# vasttrapi_pmu.net
KiCad netlist of a schematic drawn in EAGLE
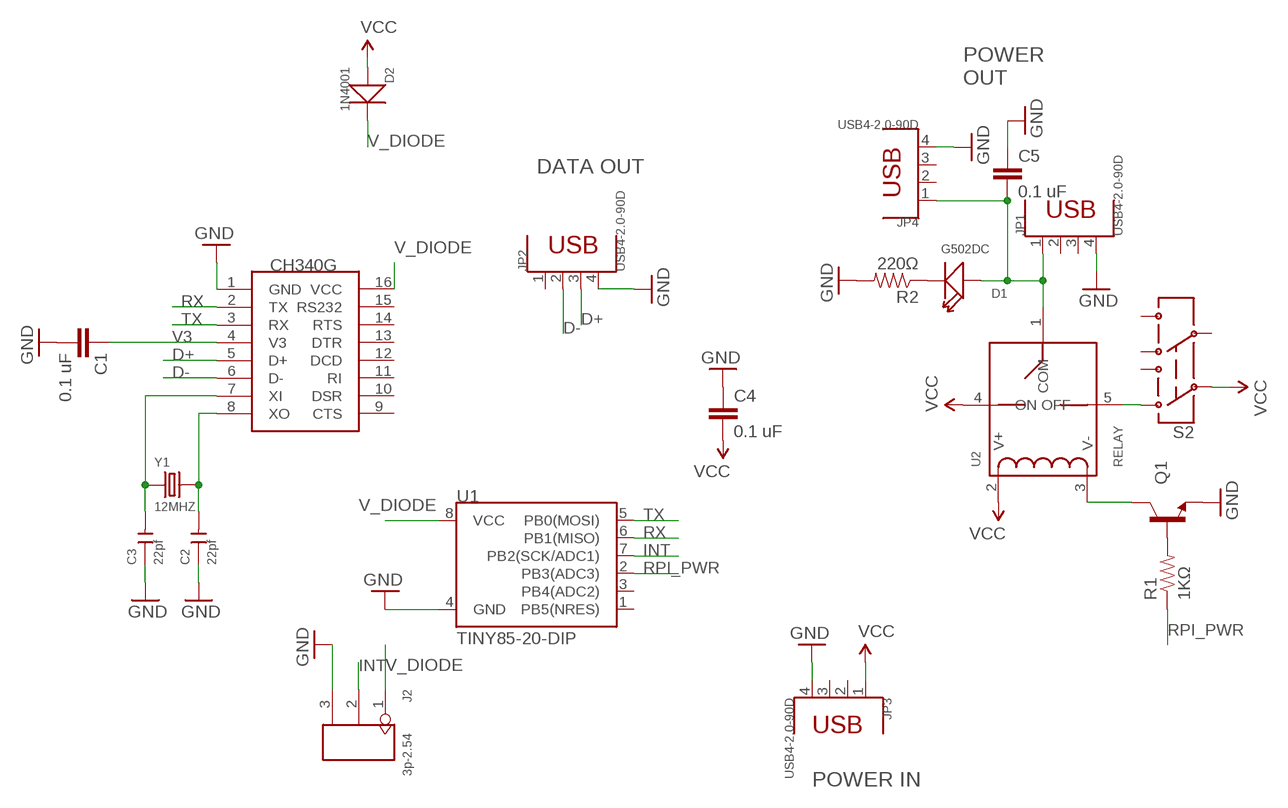
[diagram p0: schematic, sheet 1]

(export (version "E")
  (design (tool "Eeschema 10.0.6"))
  (components
    (comp (ref "C1")
      (value "0.1 uF")
      (footprint "eagle-import:CAP-PTH-SMALL-KIT")
      (libsource (lib "eagle-import") (part "0.1UF-50V-20%(PTH)KIT-EZ"))
    )
    (comp (ref "C2")
      (value "22pf")
      (footprint "eagle-import:CERAMIC-2.54")
      (fields (field (name "MPN") "CT4-0805CG220J101F3"))
      (libsource (lib "eagle-import") (part "DIP-CERAMIC-22PF-100V-5%-NPO(D5.0MM)"))
    )
    (comp (ref "C3")
      (value "22pf")
      (footprint "eagle-import:CERAMIC-2.54")
      (fields (field (name "MPN") "CT4-0805CG220J101F3"))
      (libsource (lib "eagle-import") (part "DIP-CERAMIC-22PF-100V-5%-NPO(D5.0MM)"))
    )
    (comp (ref "C4")
      (value "0.1 uF")
      (footprint "eagle-import:CAP-PTH-SMALL-KIT")
      (libsource (lib "eagle-import") (part "0.1UF-50V-20%(PTH)KIT-EZ"))
    )
    (comp (ref "C5")
      (value "0.1 uF")
      (footprint "eagle-import:CAP-PTH-SMALL-KIT")
      (libsource (lib "eagle-import") (part "0.1UF-50V-20%(PTH)KIT-EZ"))
    )
    (comp (ref "D1")
      (value "G502DC")
      (footprint "eagle-import:LED2-2.54-D5.0MM")
      (libsource (lib "eagle-import") (part "DIP-LED-GREEN-GREEN(2P-D5MM)"))
    )
    (comp (ref "D2")
      (value "1N4001")
      (footprint "eagle-import:DO-41")
      (libsource (lib "eagle-import") (part "DIP-DIODE-50V-1A-1N4001(DO-41)"))
    )
    (comp (ref "J2")
      (value "3p-2.54")
      (footprint "eagle-import:H3-2.54")
      (fields (field (name "MPN") "F185-1103A0BSYA1"))
      (libsource (lib "eagle-import") (part "DIP-BLACK-FEMALE-HEADER-VERT(3P-2.54)"))
    )
    (comp (ref "JP1")
      (value "USB4-2.0-90D")
      (footprint "eagle-import:USB4+2P-2.0-90D")
      (libsource (lib "eagle-import") (part "DIP-USB-A-TYPE-FMAL(4+2P-2.0-90D)"))
    )
    (comp (ref "JP2")
      (value "USB4-2.0-90D")
      (footprint "eagle-import:USB4+2P-2.0-90D")
      (libsource (lib "eagle-import") (part "DIP-USB-A-TYPE-FMAL(4+2P-2.0-90D)"))
    )
    (comp (ref "JP3")
      (value "USB4-2.0-90D")
      (footprint "eagle-import:USB4+2P-2.0-90D")
      (libsource (lib "eagle-import") (part "DIP-USB-A-TYPE-FMAL(4+2P-2.0-90D)"))
    )
    (comp (ref "JP4")
      (value "USB4-2.0-90D")
      (footprint "eagle-import:USB4+2P-2.0-90D")
      (libsource (lib "eagle-import") (part "DIP-USB-A-TYPE-FMAL(4+2P-2.0-90D)"))
    )
    (comp (ref "Q1")
      (value "TRANSISTOR_NPNBC547")
      (footprint "eagle-import:TO-92-AMMO")
      (libsource (lib "eagle-import") (part "TRANSISTOR_NPNBC547"))
    )
    (comp (ref "R1")
      (value "1KΩ")
      (footprint "eagle-import:AXIAL-0.4")
      (libsource (lib "eagle-import") (part "RESISTORPTH-1/4W"))
    )
    (comp (ref "R2")
      (value "220Ω")
      (footprint "eagle-import:AXIAL-0.4")
      (libsource (lib "eagle-import") (part "RESISTORPTH-1/4W"))
    )
    (comp (ref "S2")
      (value "SWITCH-DPDTOS")
      (footprint "eagle-import:OS")
      (libsource (lib "eagle-import") (part "SWITCH-DPDTOS"))
    )
    (comp (ref "U$1")
      (value "CH340G")
      (footprint "eagle-import:SOIC16")
      (libsource (lib "eagle-import") (part "CH340G"))
    )
    (comp (ref "U1")
      (value "TINY85-20-DIP")
      (footprint "eagle-import:DIP08")
      (libsource (lib "eagle-import") (part "ATTINY45TINY85-20-DIP"))
    )
    (comp (ref "U2")
      (value "RELAY")
      (footprint "eagle-import:RELAY")
      (libsource (lib "eagle-import") (part "RELAY"))
    )
    (comp (ref "Y1")
      (value "12MHZ")
      (footprint "eagle-import:HC49US")
      (fields (field (name "MPN") "HC-49US    16.000MHz"))
      (libsource (lib "eagle-import") (part "DIP-CRYSTAL-16MHZ-18PF-30PPM-40R(HC49US)"))
    )
  )
  (nets
    (net (code "1") (name "/D+") (class "Default")
      (node (ref "JP2") (pin "3") (pinfunction "2_3") (pintype "bidirectional"))
      (node (ref "U$1") (pin "5") (pinfunction "D+_5") (pintype "bidirectional"))
    )
    (net (code "2") (name "/D-") (class "Default")
      (node (ref "JP2") (pin "2") (pinfunction "3_2") (pintype "bidirectional"))
      (node (ref "U$1") (pin "6") (pinfunction "D-_6") (pintype "bidirectional"))
    )
    (net (code "3") (name "/INT") (class "Default")
      (node (ref "J2") (pin "2") (pinfunction "P$2_2") (pintype "bidirectional"))
      (node (ref "U1") (pin "7") (pinfunction "PB2(SCK/ADC1)_7") (pintype "bidirectional"))
    )
    (net (code "4") (name "/RPI_PWR") (class "Default")
      (node (ref "R1") (pin "P$1") (pinfunction "1_P$1") (pintype "passive"))
      (node (ref "U1") (pin "2") (pinfunction "PB3(ADC3)_2") (pintype "bidirectional"))
    )
    (net (code "5") (name "/RX") (class "Default")
      (node (ref "U$1") (pin "2") (pinfunction "TX_2") (pintype "bidirectional"))
      (node (ref "U1") (pin "6") (pinfunction "PB1(MISO)_6") (pintype "bidirectional"))
    )
    (net (code "6") (name "/TX") (class "Default")
      (node (ref "U$1") (pin "3") (pinfunction "RX_3") (pintype "bidirectional"))
      (node (ref "U1") (pin "5") (pinfunction "PB0(MOSI)_5") (pintype "bidirectional"))
    )
    (net (code "7") (name "/V3") (class "Default")
      (node (ref "C1") (pin "1") (pinfunction "1_1") (pintype "passive"))
      (node (ref "U$1") (pin "4") (pinfunction "V3_4") (pintype "bidirectional"))
    )
    (net (code "8") (name "/V_DIODE") (class "Default")
      (node (ref "D2") (pin "2") (pinfunction "-_2") (pintype "passive"))
      (node (ref "J2") (pin "1") (pinfunction "P$1_1") (pintype "bidirectional"))
      (node (ref "U$1") (pin "16") (pinfunction "VCC_16") (pintype "bidirectional"))
      (node (ref "U1") (pin "8") (pinfunction "VCC_8") (pintype "bidirectional"))
    )
    (net (code "9") (name "GND") (class "Default")
      (node (ref "C1") (pin "2") (pinfunction "2_2") (pintype "passive"))
      (node (ref "C2") (pin "1") (pinfunction "1_1") (pintype "passive"))
      (node (ref "C3") (pin "1") (pinfunction "1_1") (pintype "passive"))
      (node (ref "C4") (pin "1") (pinfunction "1_1") (pintype "passive"))
      (node (ref "C5") (pin "1") (pinfunction "1_1") (pintype "passive"))
      (node (ref "J2") (pin "3") (pinfunction "P$3_3") (pintype "bidirectional"))
      (node (ref "JP1") (pin "4") (pinfunction "1_4") (pintype "bidirectional"))
      (node (ref "JP2") (pin "4") (pinfunction "1_4") (pintype "bidirectional"))
      (node (ref "JP3") (pin "4") (pinfunction "1_4") (pintype "bidirectional"))
      (node (ref "JP4") (pin "4") (pinfunction "1_4") (pintype "bidirectional"))
      (node (ref "Q1") (pin "3") (pinfunction "E_3") (pintype "passive"))
      (node (ref "R2") (pin "P$2") (pinfunction "2_P$2") (pintype "passive"))
      (node (ref "U$1") (pin "1") (pinfunction "GND_1") (pintype "bidirectional"))
      (node (ref "U1") (pin "4") (pinfunction "GND_4") (pintype "bidirectional"))
    )
    (net (code "10") (name "Net-(JP1A-5)") (class "Default")
      (node (ref "C5") (pin "2") (pinfunction "2_2") (pintype "passive"))
      (node (ref "D1") (pin "+") (pinfunction "+_+") (pintype "passive"))
      (node (ref "JP1") (pin "1") (pinfunction "5_1") (pintype "bidirectional"))
      (node (ref "JP4") (pin "1") (pinfunction "5_1") (pintype "bidirectional"))
      (node (ref "U2") (pin "1") (pinfunction "COM_1") (pintype "bidirectional"))
    )
    (net (code "11") (name "Net-(Q1-B)") (class "Default")
      (node (ref "Q1") (pin "2") (pinfunction "B_2") (pintype "passive"))
      (node (ref "R1") (pin "P$2") (pinfunction "2_P$2") (pintype "passive"))
    )
    (net (code "12") (name "Net-(Q1-C)") (class "Default")
      (node (ref "Q1") (pin "1") (pinfunction "C_1") (pintype "passive"))
      (node (ref "U2") (pin "3") (pinfunction "V-_3") (pintype "bidirectional"))
    )
    (net (code "13") (name "Net-(R2-1)") (class "Default")
      (node (ref "D1") (pin "-") (pinfunction "-_-") (pintype "passive"))
      (node (ref "R2") (pin "P$1") (pinfunction "1_P$1") (pintype "passive"))
    )
    (net (code "14") (name "Net-(U$1-XI)") (class "Default")
      (node (ref "C3") (pin "2") (pinfunction "2_2") (pintype "passive"))
      (node (ref "U$1") (pin "7") (pinfunction "XI_7") (pintype "bidirectional"))
      (node (ref "Y1") (pin "1") (pinfunction "1_1") (pintype "passive"))
    )
    (net (code "15") (name "Net-(U$1-XO)") (class "Default")
      (node (ref "C2") (pin "2") (pinfunction "2_2") (pintype "passive"))
      (node (ref "U$1") (pin "8") (pinfunction "XO_8") (pintype "bidirectional"))
      (node (ref "Y1") (pin "2") (pinfunction "2_2") (pintype "passive"))
    )
    (net (code "16") (name "Net-(U2-OFF)") (class "Default")
      (node (ref "S2") (pin "1") (pinfunction "1_1") (pintype "bidirectional"))
      (node (ref "U2") (pin "5") (pinfunction "OFF_5") (pintype "bidirectional"))
    )
    (net (code "17") (name "VCC") (class "Default")
      (node (ref "C4") (pin "2") (pinfunction "2_2") (pintype "passive"))
      (node (ref "D2") (pin "1") (pinfunction "+_1") (pintype "passive"))
      (node (ref "JP3") (pin "1") (pinfunction "5_1") (pintype "bidirectional"))
      (node (ref "S2") (pin "2") (pinfunction "2_2") (pintype "bidirectional"))
      (node (ref "U2") (pin "2") (pinfunction "V+_2") (pintype "bidirectional"))
      (node (ref "U2") (pin "4") (pinfunction "ON_4") (pintype "bidirectional"))
    )
    (net (code "18") (name "unconnected-(JP1A-2-Pad3)") (class "Default")
      (node (ref "JP1") (pin "3") (pinfunction "2_3") (pintype "bidirectional"))
    )
    (net (code "19") (name "unconnected-(JP1A-3-Pad2)") (class "Default")
      (node (ref "JP1") (pin "2") (pinfunction "3_2") (pintype "bidirectional"))
    )
    (net (code "20") (name "unconnected-(JP2A-5-Pad1)") (class "Default")
      (node (ref "JP2") (pin "1") (pinfunction "5_1") (pintype "bidirectional"))
    )
    (net (code "21") (name "unconnected-(JP3A-2-Pad3)") (class "Default")
      (node (ref "JP3") (pin "3") (pinfunction "2_3") (pintype "bidirectional"))
    )
    (net (code "22") (name "unconnected-(JP3A-3-Pad2)") (class "Default")
      (node (ref "JP3") (pin "2") (pinfunction "3_2") (pintype "bidirectional"))
    )
    (net (code "23") (name "unconnected-(JP4A-2-Pad3)") (class "Default")
      (node (ref "JP4") (pin "3") (pinfunction "2_3") (pintype "bidirectional"))
    )
    (net (code "24") (name "unconnected-(JP4A-3-Pad2)") (class "Default")
      (node (ref "JP4") (pin "2") (pinfunction "3_2") (pintype "bidirectional"))
    )
    (net (code "25") (name "unconnected-(S2-Pad3)") (class "Default")
      (node (ref "S2") (pin "3") (pinfunction "3_3") (pintype "bidirectional"))
    )
    (net (code "26") (name "unconnected-(S2-Pad4)") (class "Default")
      (node (ref "S2") (pin "4") (pinfunction "4_4") (pintype "bidirectional"))
    )
    (net (code "27") (name "unconnected-(S2-Pad5)") (class "Default")
      (node (ref "S2") (pin "5") (pinfunction "5_5") (pintype "bidirectional"))
    )
    (net (code "28") (name "unconnected-(S2-Pad6)") (class "Default")
      (node (ref "S2") (pin "6") (pinfunction "6_6") (pintype "bidirectional"))
    )
    (net (code "29") (name "unconnected-(U$1-CTS-Pad9)") (class "Default")
      (node (ref "U$1") (pin "9") (pinfunction "CTS_9") (pintype "bidirectional"))
    )
    (net (code "30") (name "unconnected-(U$1-DCD-Pad12)") (class "Default")
      (node (ref "U$1") (pin "12") (pinfunction "DCD_12") (pintype "bidirectional"))
    )
    (net (code "31") (name "unconnected-(U$1-DSR-Pad10)") (class "Default")
      (node (ref "U$1") (pin "10") (pinfunction "DSR_10") (pintype "bidirectional"))
    )
    (net (code "32") (name "unconnected-(U$1-DTR-Pad13)") (class "Default")
      (node (ref "U$1") (pin "13") (pinfunction "DTR_13") (pintype "bidirectional"))
    )
    (net (code "33") (name "unconnected-(U$1-RI-Pad11)") (class "Default")
      (node (ref "U$1") (pin "11") (pinfunction "RI_11") (pintype "bidirectional"))
    )
    (net (code "34") (name "unconnected-(U$1-RS232-Pad15)") (class "Default")
      (node (ref "U$1") (pin "15") (pinfunction "RS232_15") (pintype "bidirectional"))
    )
    (net (code "35") (name "unconnected-(U$1-RTS-Pad14)") (class "Default")
      (node (ref "U$1") (pin "14") (pinfunction "RTS_14") (pintype "bidirectional"))
    )
    (net (code "36") (name "unconnected-(U1-PB4(ADC2)-Pad3)") (class "Default")
      (node (ref "U1") (pin "3") (pinfunction "PB4(ADC2)_3") (pintype "bidirectional"))
    )
    (net (code "37") (name "unconnected-(U1-PB5(NRES)-Pad1)") (class "Default")
      (node (ref "U1") (pin "1") (pinfunction "PB5(NRES)_1") (pintype "bidirectional"))
    )
  )
)
